# LED_matrix.net
KiCad netlist of a schematic drawn in EAGLE
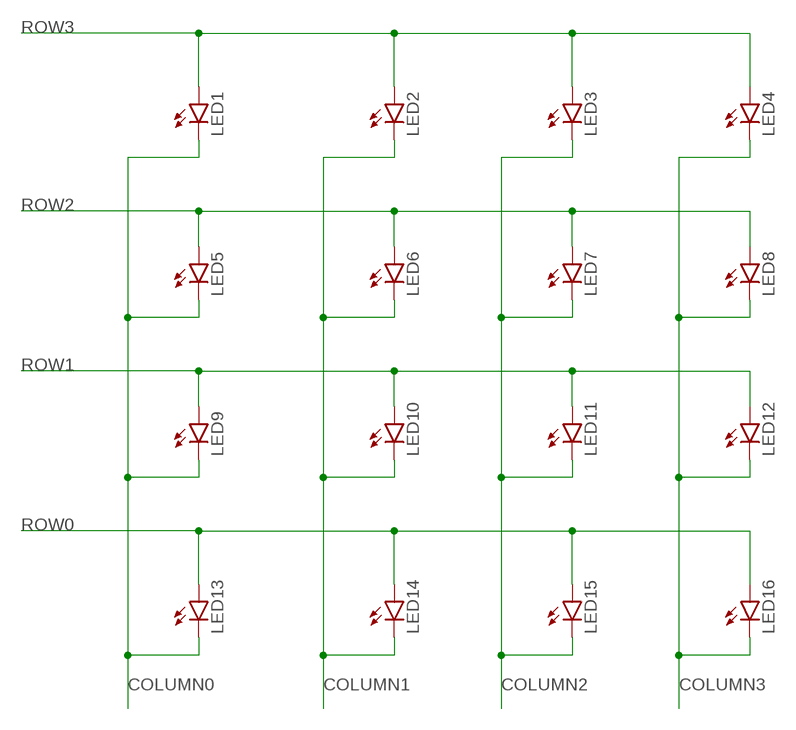
[diagram p0: schematic, sheet 1]

(export (version "E")
  (design (tool "Eeschema 10.0.6"))
  (components
    (comp (ref "LED1")
      (value "LED5MM")
      (footprint "eagle-import:LED5MM")
      (libsource (lib "eagle-import") (part "LED5MM"))
    )
    (comp (ref "LED2")
      (value "LED5MM")
      (footprint "eagle-import:LED5MM")
      (libsource (lib "eagle-import") (part "LED5MM"))
    )
    (comp (ref "LED3")
      (value "LED5MM")
      (footprint "eagle-import:LED5MM")
      (libsource (lib "eagle-import") (part "LED5MM"))
    )
    (comp (ref "LED4")
      (value "LED5MM")
      (footprint "eagle-import:LED5MM")
      (libsource (lib "eagle-import") (part "LED5MM"))
    )
    (comp (ref "LED5")
      (value "LED5MM")
      (footprint "eagle-import:LED5MM")
      (libsource (lib "eagle-import") (part "LED5MM"))
    )
    (comp (ref "LED6")
      (value "LED5MM")
      (footprint "eagle-import:LED5MM")
      (libsource (lib "eagle-import") (part "LED5MM"))
    )
    (comp (ref "LED7")
      (value "LED5MM")
      (footprint "eagle-import:LED5MM")
      (libsource (lib "eagle-import") (part "LED5MM"))
    )
    (comp (ref "LED8")
      (value "LED5MM")
      (footprint "eagle-import:LED5MM")
      (libsource (lib "eagle-import") (part "LED5MM"))
    )
    (comp (ref "LED9")
      (value "LED5MM")
      (footprint "eagle-import:LED5MM")
      (libsource (lib "eagle-import") (part "LED5MM"))
    )
    (comp (ref "LED10")
      (value "LED5MM")
      (footprint "eagle-import:LED5MM")
      (libsource (lib "eagle-import") (part "LED5MM"))
    )
    (comp (ref "LED11")
      (value "LED5MM")
      (footprint "eagle-import:LED5MM")
      (libsource (lib "eagle-import") (part "LED5MM"))
    )
    (comp (ref "LED12")
      (value "LED5MM")
      (footprint "eagle-import:LED5MM")
      (libsource (lib "eagle-import") (part "LED5MM"))
    )
    (comp (ref "LED13")
      (value "LED5MM")
      (footprint "eagle-import:LED5MM")
      (libsource (lib "eagle-import") (part "LED5MM"))
    )
    (comp (ref "LED14")
      (value "LED5MM")
      (footprint "eagle-import:LED5MM")
      (libsource (lib "eagle-import") (part "LED5MM"))
    )
    (comp (ref "LED15")
      (value "LED5MM")
      (footprint "eagle-import:LED5MM")
      (libsource (lib "eagle-import") (part "LED5MM"))
    )
    (comp (ref "LED16")
      (value "LED5MM")
      (footprint "eagle-import:LED5MM")
      (libsource (lib "eagle-import") (part "LED5MM"))
    )
  )
  (nets
    (net (code "1") (name "/COLUMN0") (class "Default")
      (node (ref "LED1") (pin "K") (pinfunction "C_K") (pintype "passive"))
      (node (ref "LED13") (pin "K") (pinfunction "C_K") (pintype "passive"))
      (node (ref "LED5") (pin "K") (pinfunction "C_K") (pintype "passive"))
      (node (ref "LED9") (pin "K") (pinfunction "C_K") (pintype "passive"))
    )
    (net (code "2") (name "/COLUMN1") (class "Default")
      (node (ref "LED10") (pin "K") (pinfunction "C_K") (pintype "passive"))
      (node (ref "LED14") (pin "K") (pinfunction "C_K") (pintype "passive"))
      (node (ref "LED2") (pin "K") (pinfunction "C_K") (pintype "passive"))
      (node (ref "LED6") (pin "K") (pinfunction "C_K") (pintype "passive"))
    )
    (net (code "3") (name "/COLUMN2") (class "Default")
      (node (ref "LED11") (pin "K") (pinfunction "C_K") (pintype "passive"))
      (node (ref "LED15") (pin "K") (pinfunction "C_K") (pintype "passive"))
      (node (ref "LED3") (pin "K") (pinfunction "C_K") (pintype "passive"))
      (node (ref "LED7") (pin "K") (pinfunction "C_K") (pintype "passive"))
    )
    (net (code "4") (name "/COLUMN3") (class "Default")
      (node (ref "LED12") (pin "K") (pinfunction "C_K") (pintype "passive"))
      (node (ref "LED16") (pin "K") (pinfunction "C_K") (pintype "passive"))
      (node (ref "LED4") (pin "K") (pinfunction "C_K") (pintype "passive"))
      (node (ref "LED8") (pin "K") (pinfunction "C_K") (pintype "passive"))
    )
    (net (code "5") (name "/ROW0") (class "Default")
      (node (ref "LED13") (pin "A") (pinfunction "A_A") (pintype "passive"))
      (node (ref "LED14") (pin "A") (pinfunction "A_A") (pintype "passive"))
      (node (ref "LED15") (pin "A") (pinfunction "A_A") (pintype "passive"))
      (node (ref "LED16") (pin "A") (pinfunction "A_A") (pintype "passive"))
    )
    (net (code "6") (name "/ROW1") (class "Default")
      (node (ref "LED10") (pin "A") (pinfunction "A_A") (pintype "passive"))
      (node (ref "LED11") (pin "A") (pinfunction "A_A") (pintype "passive"))
      (node (ref "LED12") (pin "A") (pinfunction "A_A") (pintype "passive"))
      (node (ref "LED9") (pin "A") (pinfunction "A_A") (pintype "passive"))
    )
    (net (code "7") (name "/ROW2") (class "Default")
      (node (ref "LED5") (pin "A") (pinfunction "A_A") (pintype "passive"))
      (node (ref "LED6") (pin "A") (pinfunction "A_A") (pintype "passive"))
      (node (ref "LED7") (pin "A") (pinfunction "A_A") (pintype "passive"))
      (node (ref "LED8") (pin "A") (pinfunction "A_A") (pintype "passive"))
    )
    (net (code "8") (name "/ROW3") (class "Default")
      (node (ref "LED1") (pin "A") (pinfunction "A_A") (pintype "passive"))
      (node (ref "LED2") (pin "A") (pinfunction "A_A") (pintype "passive"))
      (node (ref "LED3") (pin "A") (pinfunction "A_A") (pintype "passive"))
      (node (ref "LED4") (pin "A") (pinfunction "A_A") (pintype "passive"))
    )
  )
)
